# CW308T_SAM4L_Micro.net
KiCad netlist of a schematic drawn in Altium Designer
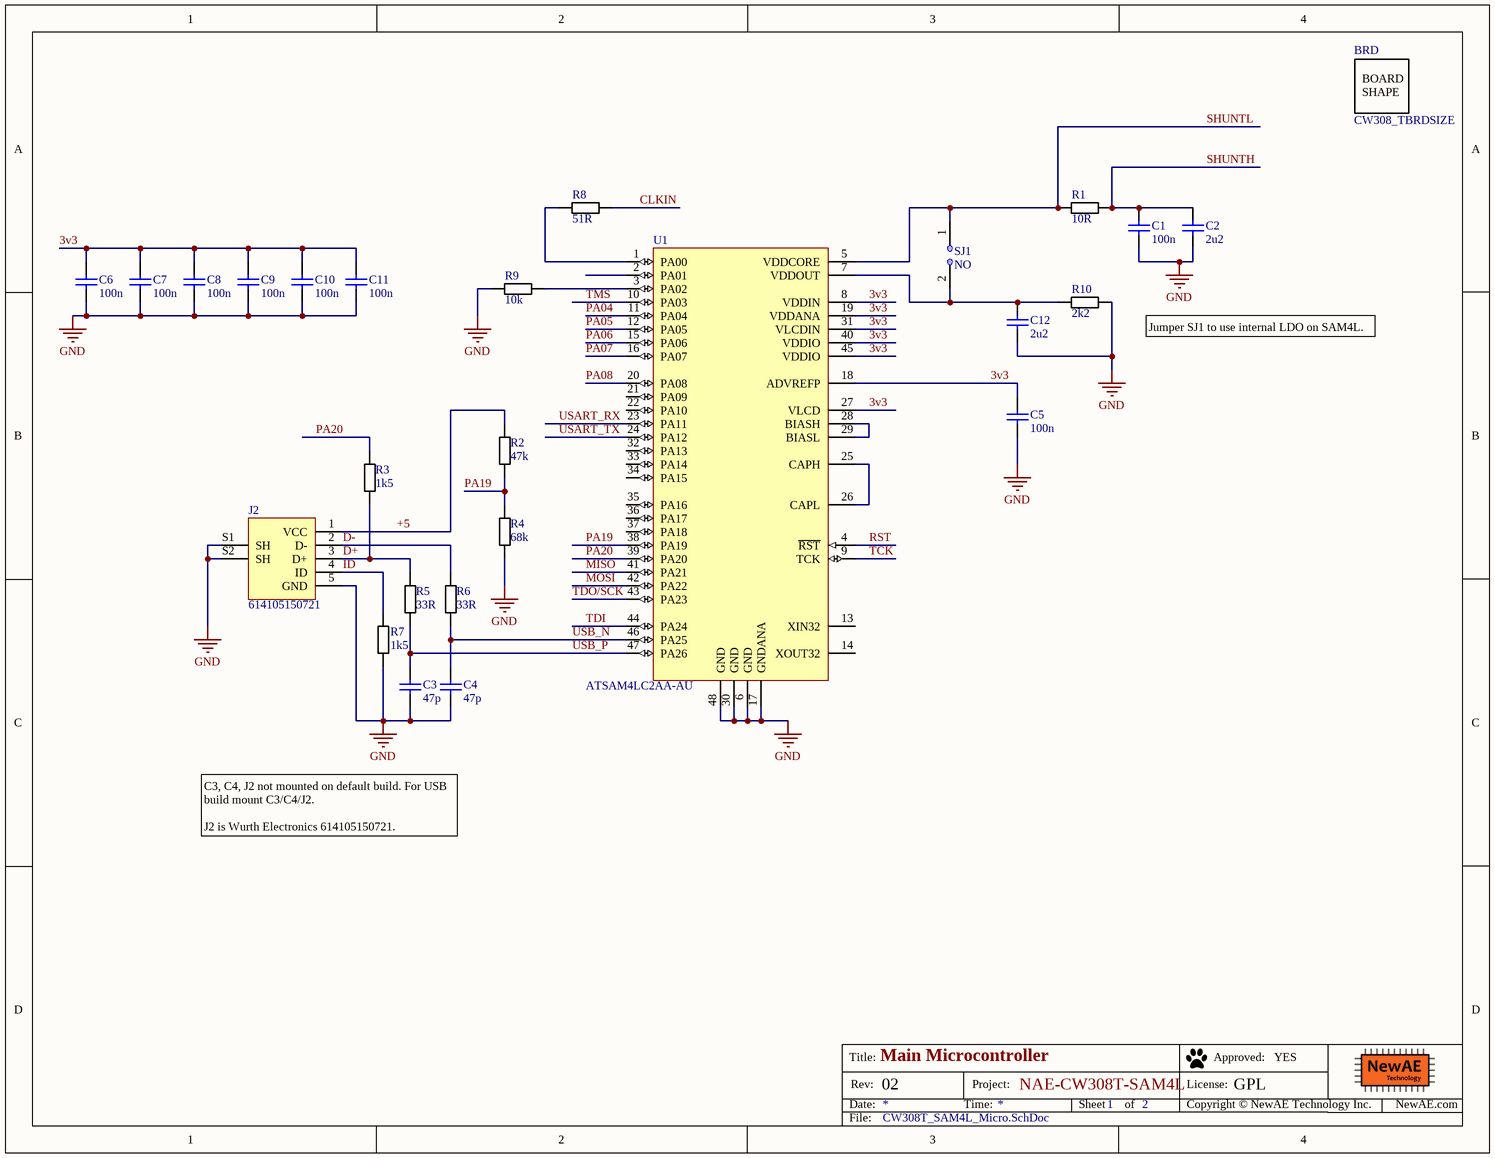
[diagram p0: CW308T_SAM4L_Micro.SchDoc]

(export (version "E")
  (design (tool "Eeschema 10.0.6"))
  (components
    (comp (ref "BRD")
      (value "CW308_TBRDSIZE")
      (footprint "CW308T_TBOARD_DEFSIZE")
      (description "308T Board Outline (Layer 1)")
      (fields (field (name "PART NUMBER") "CW308T_BRDSHAPE_DEFAULT"))
      (libsource (lib "NewAE_AltiumLib") (part "CW308_TBRDSIZE"))
    )
    (comp (ref "C1")
      (value "100n")
      (footprint "CAPC0603_M")
      (description "100n, 0603")
      (fields (field (name "PART NUMBER") "CCHIP-100n-0603"))
      (libsource (lib "NewAE_AltiumLib") (part "CAP"))
    )
    (comp (ref "C2")
      (value "2u2")
      (footprint "CAPC0603_M")
      (description "2u2, 0603")
      (fields (field (name "PART NUMBER") "CCHIP-2u2-0603"))
      (libsource (lib "NewAE_AltiumLib") (part "CAP"))
    )
    (comp (ref "C3")
      (value "47p")
      (footprint "CAPC0603_M")
      (description "47p, 0603")
      (fields (field (name "PART NUMBER") "CCHIP-47p-0603"))
      (libsource (lib "NewAE_AltiumLib") (part "CAP"))
    )
    (comp (ref "C4")
      (value "47p")
      (footprint "CAPC0603_M")
      (description "47p, 0603")
      (fields (field (name "PART NUMBER") "CCHIP-47p-0603"))
      (libsource (lib "NewAE_AltiumLib") (part "CAP"))
    )
    (comp (ref "C5")
      (value "100n")
      (footprint "CAPC0603_M")
      (description "100n, 0603")
      (fields (field (name "PART NUMBER") "CCHIP-100n-0603"))
      (libsource (lib "NewAE_AltiumLib") (part "CAP"))
    )
    (comp (ref "C6")
      (value "100n")
      (footprint "CAPC0603_M")
      (description "100n, 0603")
      (fields (field (name "PART NUMBER") "CCHIP-100n-0603"))
      (libsource (lib "NewAE_AltiumLib") (part "CAP"))
    )
    (comp (ref "C7")
      (value "100n")
      (footprint "CAPC0603_M")
      (description "100n, 0603")
      (fields (field (name "PART NUMBER") "CCHIP-100n-0603"))
      (libsource (lib "NewAE_AltiumLib") (part "CAP"))
    )
    (comp (ref "C8")
      (value "100n")
      (footprint "CAPC0603_M")
      (description "100n, 0603")
      (fields (field (name "PART NUMBER") "CCHIP-100n-0603"))
      (libsource (lib "NewAE_AltiumLib") (part "CAP"))
    )
    (comp (ref "C9")
      (value "100n")
      (footprint "CAPC0603_M")
      (description "100n, 0603")
      (fields (field (name "PART NUMBER") "CCHIP-100n-0603"))
      (libsource (lib "NewAE_AltiumLib") (part "CAP"))
    )
    (comp (ref "C10")
      (value "100n")
      (footprint "CAPC0603_M")
      (description "100n, 0603")
      (fields (field (name "PART NUMBER") "CCHIP-100n-0603"))
      (libsource (lib "NewAE_AltiumLib") (part "CAP"))
    )
    (comp (ref "C11")
      (value "100n")
      (footprint "CAPC0603_M")
      (description "100n, 0603")
      (fields (field (name "PART NUMBER") "CCHIP-100n-0603"))
      (libsource (lib "NewAE_AltiumLib") (part "CAP"))
    )
    (comp (ref "C12")
      (value "2u2")
      (footprint "CAPC0603_M")
      (description "2u2, 0603")
      (fields (field (name "PART NUMBER") "CCHIP-2u2-0603"))
      (libsource (lib "NewAE_AltiumLib") (part "CAP"))
    )
    (comp (ref "J2")
      (value "614105150721")
      (footprint "614105150721")
      (description "USB, 5-pin, Upright")
      (libsource (lib "NewAE_AltiumLib") (part "USB_5PIN_2SHIELD"))
    )
    (comp (ref "R1")
      (value "10R")
      (footprint "RESC1608X55N")
      (description "10R res, 0603, 1%, 1/10W")
      (fields (field (name "PART NUMBER") "RCHIP-10R-0603") (field (name "TOLERANCE") "1%"))
      (libsource (lib "") (part "RES-EU_1"))
    )
    (comp (ref "R2")
      (value "47k")
      (footprint "RESC1608X55N")
      (description "47k res, 0603, 1%, 1/10W")
      (fields (field (name "PART NUMBER") "RCHIP-47K-0603") (field (name "TOLERANCE") "1%"))
      (libsource (lib "NewAE_AltiumLib") (part "RES-EU"))
    )
    (comp (ref "R3")
      (value "1k5")
      (footprint "RESC1608X55N")
      (description "1k5 res, 0603, 1%, 1/10W")
      (fields (field (name "PART NUMBER") "RCHIP-1K5-0603") (field (name "TOLERANCE") "1%"))
      (libsource (lib "") (part "RES-EU_2"))
    )
    (comp (ref "R4")
      (value "68k")
      (footprint "RESC1608X55N")
      (description "68k res, 0603, 1%, 1/10W")
      (fields (field (name "PART NUMBER") "RCHIP-68K-0603") (field (name "TOLERANCE") "1%"))
      (libsource (lib "NewAE_AltiumLib") (part "RES-EU"))
    )
    (comp (ref "R5")
      (value "33R")
      (footprint "RESC1608X55N")
      (description "33R res, 0603, 1%, 1/10W")
      (fields (field (name "PART NUMBER") "RCHIP-33R-0603") (field (name "TOLERANCE") "1%"))
      (libsource (lib "") (part "RES-EU_2"))
    )
    (comp (ref "R6")
      (value "33R")
      (footprint "RESC1608X55N")
      (description "33R res, 0603, 1%, 1/10W")
      (fields (field (name "PART NUMBER") "RCHIP-33R-0603") (field (name "TOLERANCE") "1%"))
      (libsource (lib "NewAE_AltiumLib") (part "RES-EU"))
    )
    (comp (ref "R7")
      (value "1k5")
      (footprint "RESC1608X55N")
      (description "1k5 res, 0603, 1%, 1/10W")
      (fields (field (name "PART NUMBER") "RCHIP-1K5-0603") (field (name "TOLERANCE") "1%"))
      (libsource (lib "NewAE_AltiumLib") (part "RES-EU"))
    )
    (comp (ref "R8")
      (value "51R")
      (footprint "RESC1608X55N")
      (description "51R res, 0603, 1%, 1/10W")
      (fields (field (name "PART NUMBER") "RCHIP-51R-0603") (field (name "TOLERANCE") "1%"))
      (libsource (lib "") (part "RES-EU_1"))
    )
    (comp (ref "R9")
      (value "10k")
      (footprint "RESC1608X55N")
      (description "10k res, 0603, 1%, 1/10W")
      (fields (field (name "PART NUMBER") "RCHIP-10K-0603") (field (name "TOLERANCE") "1%"))
      (libsource (lib "") (part "RES-EU_1"))
    )
    (comp (ref "R10")
      (value "2k2")
      (footprint "RESC1608X55N")
      (description "2k2 res, 0603, 1%, 1/10W")
      (fields (field (name "PART NUMBER") "RCHIP-2K2-0603") (field (name "TOLERANCE") "1%"))
      (libsource (lib "") (part "RES-EU_1"))
    )
    (comp (ref "SJ1")
      (value "NO")
      (footprint "SJ_2S_NO")
      (description "Solder Jumper, NO")
      (fields (field (name "PART NUMBER") "SJ_2S_NO"))
      (libsource (lib "NewAE_AltiumLib") (part "SJ_2S_NO"))
    )
    (comp (ref "U1")
      (value "ATSAM4LC2AA-AU")
      (footprint "TSQFP50P900X900X120-48N")
      (description "Atmel, SAM4L, 48-TQFP")
      (libsource (lib "NewAE_AltiumLib") (part "ATSAM4LxxA"))
    )
  )
  (nets
    (net (code "1") (name "/+5") (class "Default")
      (node (ref "J2") (pin "1") (pinfunction "VCC_1") (pintype "passive"))
      (node (ref "R2") (pin "1") (pinfunction "1_1") (pintype "passive"))
    )
    (net (code "2") (name "/3v3") (class "Default")
      (node (ref "C10") (pin "1") (pinfunction "1_1") (pintype "passive"))
      (node (ref "C11") (pin "1") (pinfunction "1_1") (pintype "passive"))
      (node (ref "C5") (pin "1") (pinfunction "1_1") (pintype "passive"))
      (node (ref "C6") (pin "1") (pinfunction "1_1") (pintype "passive"))
      (node (ref "C7") (pin "1") (pinfunction "1_1") (pintype "passive"))
      (node (ref "C8") (pin "1") (pinfunction "1_1") (pintype "passive"))
      (node (ref "C9") (pin "1") (pinfunction "1_1") (pintype "passive"))
      (node (ref "U1") (pin "18") (pinfunction "ADVREFP_18") (pintype "passive"))
      (node (ref "U1") (pin "19") (pinfunction "VDDANA_19") (pintype "power_in"))
      (node (ref "U1") (pin "27") (pinfunction "VLCD_27") (pintype "passive"))
      (node (ref "U1") (pin "31") (pinfunction "VLCDIN_31") (pintype "power_in"))
      (node (ref "U1") (pin "40") (pinfunction "VDDIO_40") (pintype "power_in"))
      (node (ref "U1") (pin "45") (pinfunction "VDDIO_45") (pintype "power_in"))
      (node (ref "U1") (pin "8") (pinfunction "VDDIN_8") (pintype "power_in"))
    )
    (net (code "3") (name "/CLKIN") (class "Default")
      (node (ref "R8") (pin "2") (pinfunction "2_2") (pintype "passive"))
    )
    (net (code "4") (name "/D+") (class "Default")
      (node (ref "J2") (pin "3") (pinfunction "D+_3") (pintype "passive"))
      (node (ref "R3") (pin "1") (pinfunction "1_1") (pintype "passive"))
      (node (ref "R5") (pin "2") (pinfunction "2_2") (pintype "passive"))
    )
    (net (code "5") (name "/D-") (class "Default")
      (node (ref "J2") (pin "2") (pinfunction "D-_2") (pintype "passive"))
      (node (ref "R6") (pin "1") (pinfunction "1_1") (pintype "passive"))
    )
    (net (code "6") (name "/ID") (class "Default")
      (node (ref "J2") (pin "4") (pinfunction "ID_4") (pintype "power_in"))
      (node (ref "R7") (pin "1") (pinfunction "1_1") (pintype "passive"))
    )
    (net (code "7") (name "/MISO") (class "Default")
      (node (ref "U1") (pin "41") (pinfunction "PA21_41") (pintype "bidirectional"))
    )
    (net (code "8") (name "/MOSI") (class "Default")
      (node (ref "U1") (pin "42") (pinfunction "PA22_42") (pintype "bidirectional"))
    )
    (net (code "9") (name "/PA04") (class "Default")
      (node (ref "U1") (pin "11") (pinfunction "PA04_11") (pintype "bidirectional"))
    )
    (net (code "10") (name "/PA05") (class "Default")
      (node (ref "U1") (pin "12") (pinfunction "PA05_12") (pintype "bidirectional"))
    )
    (net (code "11") (name "/PA06") (class "Default")
      (node (ref "U1") (pin "15") (pinfunction "PA06_15") (pintype "bidirectional"))
    )
    (net (code "12") (name "/PA07") (class "Default")
      (node (ref "U1") (pin "16") (pinfunction "PA07_16") (pintype "bidirectional"))
    )
    (net (code "13") (name "/PA08") (class "Default")
      (node (ref "U1") (pin "20") (pinfunction "PA08_20") (pintype "bidirectional"))
    )
    (net (code "14") (name "/PA19") (class "Default")
      (node (ref "R2") (pin "2") (pinfunction "2_2") (pintype "passive"))
      (node (ref "R4") (pin "1") (pinfunction "1_1") (pintype "passive"))
      (node (ref "U1") (pin "38") (pinfunction "PA19_38") (pintype "bidirectional"))
    )
    (net (code "15") (name "/PA20") (class "Default")
      (node (ref "R3") (pin "2") (pinfunction "2_2") (pintype "passive"))
      (node (ref "U1") (pin "39") (pinfunction "PA20_39") (pintype "bidirectional"))
    )
    (net (code "16") (name "/RST") (class "Default")
      (node (ref "U1") (pin "4") (pinfunction "~{RST}_4") (pintype "input"))
    )
    (net (code "17") (name "/SHUNTH") (class "Default")
      (node (ref "C1") (pin "1") (pinfunction "1_1") (pintype "passive"))
      (node (ref "C2") (pin "1") (pinfunction "1_1") (pintype "passive"))
      (node (ref "R1") (pin "2") (pinfunction "2_2") (pintype "passive"))
    )
    (net (code "18") (name "/SHUNTL") (class "Default")
      (node (ref "R1") (pin "1") (pinfunction "1_1") (pintype "passive"))
      (node (ref "SJ1") (pin "1") (pinfunction "1_1") (pintype "passive"))
      (node (ref "U1") (pin "5") (pinfunction "VDDCORE_5") (pintype "passive"))
    )
    (net (code "19") (name "/TCK") (class "Default")
      (node (ref "U1") (pin "9") (pinfunction "TCK_9") (pintype "bidirectional"))
    )
    (net (code "20") (name "/TDI") (class "Default")
      (node (ref "U1") (pin "44") (pinfunction "PA24_44") (pintype "bidirectional"))
    )
    (net (code "21") (name "/TDO{slash}SCK") (class "Default")
      (node (ref "U1") (pin "43") (pinfunction "PA23_43") (pintype "bidirectional"))
    )
    (net (code "22") (name "/TMS") (class "Default")
      (node (ref "U1") (pin "10") (pinfunction "PA03_10") (pintype "bidirectional"))
    )
    (net (code "23") (name "/USART_RX") (class "Default")
      (node (ref "U1") (pin "23") (pinfunction "PA11_23") (pintype "bidirectional"))
    )
    (net (code "24") (name "/USART_TX") (class "Default")
      (node (ref "U1") (pin "24") (pinfunction "PA12_24") (pintype "bidirectional"))
    )
    (net (code "25") (name "/USB_N") (class "Default")
      (node (ref "C4") (pin "1") (pinfunction "1_1") (pintype "passive"))
      (node (ref "R6") (pin "2") (pinfunction "2_2") (pintype "passive"))
      (node (ref "U1") (pin "46") (pinfunction "PA25_46") (pintype "bidirectional"))
    )
    (net (code "26") (name "/USB_P") (class "Default")
      (node (ref "C3") (pin "1") (pinfunction "1_1") (pintype "passive"))
      (node (ref "R5") (pin "1") (pinfunction "1_1") (pintype "passive"))
      (node (ref "U1") (pin "47") (pinfunction "PA26_47") (pintype "bidirectional"))
    )
    (net (code "27") (name "GND") (class "Default")
      (node (ref "C1") (pin "2") (pinfunction "2_2") (pintype "passive"))
      (node (ref "C10") (pin "2") (pinfunction "2_2") (pintype "passive"))
      (node (ref "C11") (pin "2") (pinfunction "2_2") (pintype "passive"))
      (node (ref "C12") (pin "2") (pinfunction "2_2") (pintype "passive"))
      (node (ref "C2") (pin "2") (pinfunction "2_2") (pintype "passive"))
      (node (ref "C3") (pin "2") (pinfunction "2_2") (pintype "passive"))
      (node (ref "C4") (pin "2") (pinfunction "2_2") (pintype "passive"))
      (node (ref "C5") (pin "2") (pinfunction "2_2") (pintype "passive"))
      (node (ref "C6") (pin "2") (pinfunction "2_2") (pintype "passive"))
      (node (ref "C7") (pin "2") (pinfunction "2_2") (pintype "passive"))
      (node (ref "C8") (pin "2") (pinfunction "2_2") (pintype "passive"))
      (node (ref "C9") (pin "2") (pinfunction "2_2") (pintype "passive"))
      (node (ref "J2") (pin "5") (pinfunction "GND_5") (pintype "power_in"))
      (node (ref "J2") (pin "S1") (pinfunction "SH_S1") (pintype "passive"))
      (node (ref "J2") (pin "S2") (pinfunction "SH_S2") (pintype "passive"))
      (node (ref "R10") (pin "2") (pinfunction "2_2") (pintype "passive"))
      (node (ref "R4") (pin "2") (pinfunction "2_2") (pintype "passive"))
      (node (ref "R7") (pin "2") (pinfunction "2_2") (pintype "passive"))
      (node (ref "R9") (pin "1") (pinfunction "1_1") (pintype "passive"))
      (node (ref "U1") (pin "17") (pinfunction "GNDANA_17") (pintype "power_in"))
      (node (ref "U1") (pin "30") (pinfunction "GND_30") (pintype "power_in"))
      (node (ref "U1") (pin "48") (pinfunction "GND_48") (pintype "power_in"))
      (node (ref "U1") (pin "6") (pinfunction "GND_6") (pintype "power_in"))
    )
    (net (code "28") (name "Net-(U1-BIASH)") (class "Default")
      (node (ref "U1") (pin "28") (pinfunction "BIASH_28") (pintype "passive"))
      (node (ref "U1") (pin "29") (pinfunction "BIASL_29") (pintype "passive"))
    )
    (net (code "29") (name "Net-(U1-CAPH)") (class "Default")
      (node (ref "U1") (pin "25") (pinfunction "CAPH_25") (pintype "passive"))
      (node (ref "U1") (pin "26") (pinfunction "CAPL_26") (pintype "passive"))
    )
    (net (code "30") (name "Net-(U1-PA00)") (class "Default")
      (node (ref "R8") (pin "1") (pinfunction "1_1") (pintype "passive"))
      (node (ref "U1") (pin "1") (pinfunction "PA00_1") (pintype "bidirectional"))
    )
    (net (code "31") (name "Net-(U1-PA02)") (class "Default")
      (node (ref "R9") (pin "2") (pinfunction "2_2") (pintype "passive"))
      (node (ref "U1") (pin "3") (pinfunction "PA02_3") (pintype "bidirectional"))
    )
    (net (code "32") (name "Net-(U1-VDDOUT)") (class "Default")
      (node (ref "C12") (pin "1") (pinfunction "1_1") (pintype "passive"))
      (node (ref "R10") (pin "1") (pinfunction "1_1") (pintype "passive"))
      (node (ref "SJ1") (pin "2") (pinfunction "2_2") (pintype "passive"))
      (node (ref "U1") (pin "7") (pinfunction "VDDOUT_7") (pintype "passive"))
    )
    (net (code "33") (name "unconnected-(U1-PA01-Pad2)") (class "Default")
      (node (ref "U1") (pin "2") (pinfunction "PA01_2") (pintype "bidirectional"))
    )
    (net (code "34") (name "unconnected-(U1-PA09-Pad21)") (class "Default")
      (node (ref "U1") (pin "21") (pinfunction "PA09_21") (pintype "bidirectional"))
    )
    (net (code "35") (name "unconnected-(U1-PA10-Pad22)") (class "Default")
      (node (ref "U1") (pin "22") (pinfunction "PA10_22") (pintype "bidirectional"))
    )
    (net (code "36") (name "unconnected-(U1-PA13-Pad32)") (class "Default")
      (node (ref "U1") (pin "32") (pinfunction "PA13_32") (pintype "bidirectional"))
    )
    (net (code "37") (name "unconnected-(U1-PA14-Pad33)") (class "Default")
      (node (ref "U1") (pin "33") (pinfunction "PA14_33") (pintype "bidirectional"))
    )
    (net (code "38") (name "unconnected-(U1-PA15-Pad34)") (class "Default")
      (node (ref "U1") (pin "34") (pinfunction "PA15_34") (pintype "bidirectional"))
    )
    (net (code "39") (name "unconnected-(U1-PA16-Pad35)") (class "Default")
      (node (ref "U1") (pin "35") (pinfunction "PA16_35") (pintype "bidirectional"))
    )
    (net (code "40") (name "unconnected-(U1-PA17-Pad36)") (class "Default")
      (node (ref "U1") (pin "36") (pinfunction "PA17_36") (pintype "bidirectional"))
    )
    (net (code "41") (name "unconnected-(U1-PA18-Pad37)") (class "Default")
      (node (ref "U1") (pin "37") (pinfunction "PA18_37") (pintype "bidirectional"))
    )
    (net (code "42") (name "unconnected-(U1-XIN32-Pad13)") (class "Default")
      (node (ref "U1") (pin "13") (pinfunction "XIN32_13") (pintype "passive"))
    )
    (net (code "43") (name "unconnected-(U1-XOUT32-Pad14)") (class "Default")
      (node (ref "U1") (pin "14") (pinfunction "XOUT32_14") (pintype "passive"))
    )
  )
)
